# LiIonLader_1ZelleMax800mA.net
KiCad netlist of a schematic drawn in EAGLE
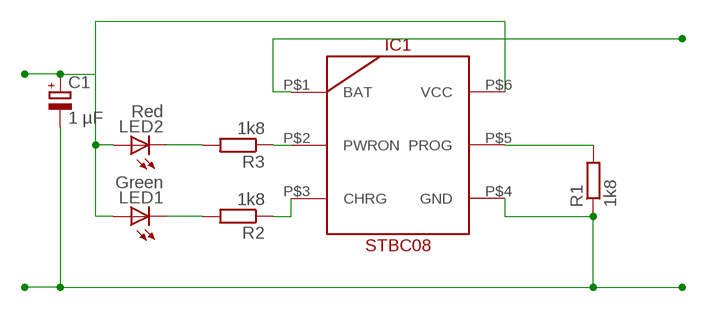
[diagram p0: schematic, sheet 1]

(export (version "E")
  (design (tool "Eeschema 10.0.6"))
  (components
    (comp (ref "C1")
      (value "1 µF")
      (footprint "eagle-import:E1,8-4")
      (libsource (lib "eagle-import") (part "CPOL-EUE1.8-4"))
    )
    (comp (ref "IC1")
      (value "STBC08")
      (footprint "eagle-import:DFN6")
      (libsource (lib "eagle-import") (part "STBC08"))
    )
    (comp (ref "LED1")
      (value "Green")
      (footprint "eagle-import:LED3MM")
      (libsource (lib "eagle-import") (part "LED3MM"))
    )
    (comp (ref "LED2")
      (value "Red")
      (footprint "eagle-import:LED3MM")
      (libsource (lib "eagle-import") (part "LED3MM"))
    )
    (comp (ref "R1")
      (value "1k8")
      (footprint "eagle-import:0204_5")
      (libsource (lib "eagle-import") (part "R-EU_0204/5"))
    )
    (comp (ref "R2")
      (value "1k8")
      (footprint "eagle-import:0204_5")
      (libsource (lib "eagle-import") (part "R-EU_0204/5"))
    )
    (comp (ref "R3")
      (value "1k8")
      (footprint "eagle-import:0204_5")
      (libsource (lib "eagle-import") (part "R-EU_0204/5"))
    )
  )
  (nets
    (net (code "1") (name "Net-(IC1-CHRG)") (class "Default")
      (node (ref "IC1") (pin "P$3") (pinfunction "CHRG_P$3") (pintype "open_collector"))
      (node (ref "R2") (pin "1") (pinfunction "1_1") (pintype "passive"))
    )
    (net (code "2") (name "Net-(IC1-GND)") (class "Default")
      (node (ref "C1") (pin "-") (pinfunction "-_-") (pintype "passive"))
      (node (ref "IC1") (pin "P$4") (pinfunction "GND_P$4") (pintype "power_in"))
      (node (ref "R1") (pin "1") (pinfunction "1_1") (pintype "passive"))
    )
    (net (code "3") (name "Net-(IC1-PROG)") (class "Default")
      (node (ref "IC1") (pin "P$5") (pinfunction "PROG_P$5") (pintype "passive"))
      (node (ref "R1") (pin "2") (pinfunction "2_2") (pintype "passive"))
    )
    (net (code "4") (name "Net-(IC1-PWRON)") (class "Default")
      (node (ref "IC1") (pin "P$2") (pinfunction "PWRON_P$2") (pintype "open_collector"))
      (node (ref "R3") (pin "1") (pinfunction "1_1") (pintype "passive"))
    )
    (net (code "5") (name "Net-(IC1-VCC)") (class "Default")
      (node (ref "C1") (pin "+") (pinfunction "+_+") (pintype "passive"))
      (node (ref "IC1") (pin "P$6") (pinfunction "VCC_P$6") (pintype "power_in"))
      (node (ref "LED1") (pin "A") (pinfunction "A_A") (pintype "passive"))
      (node (ref "LED2") (pin "A") (pinfunction "A_A") (pintype "passive"))
    )
    (net (code "6") (name "Net-(LED1-C)") (class "Default")
      (node (ref "LED1") (pin "K") (pinfunction "C_K") (pintype "passive"))
      (node (ref "R2") (pin "2") (pinfunction "2_2") (pintype "passive"))
    )
    (net (code "7") (name "Net-(LED2-C)") (class "Default")
      (node (ref "LED2") (pin "K") (pinfunction "C_K") (pintype "passive"))
      (node (ref "R3") (pin "2") (pinfunction "2_2") (pintype "passive"))
    )
    (net (code "8") (name "unconnected-(IC1-BAT-PadP$1)") (class "Default")
      (node (ref "IC1") (pin "P$1") (pinfunction "BAT_P$1") (pintype "output"))
    )
  )
)
